# LF_SDD_AC_DC.net
KiCad netlist of a schematic drawn in Altium Designer
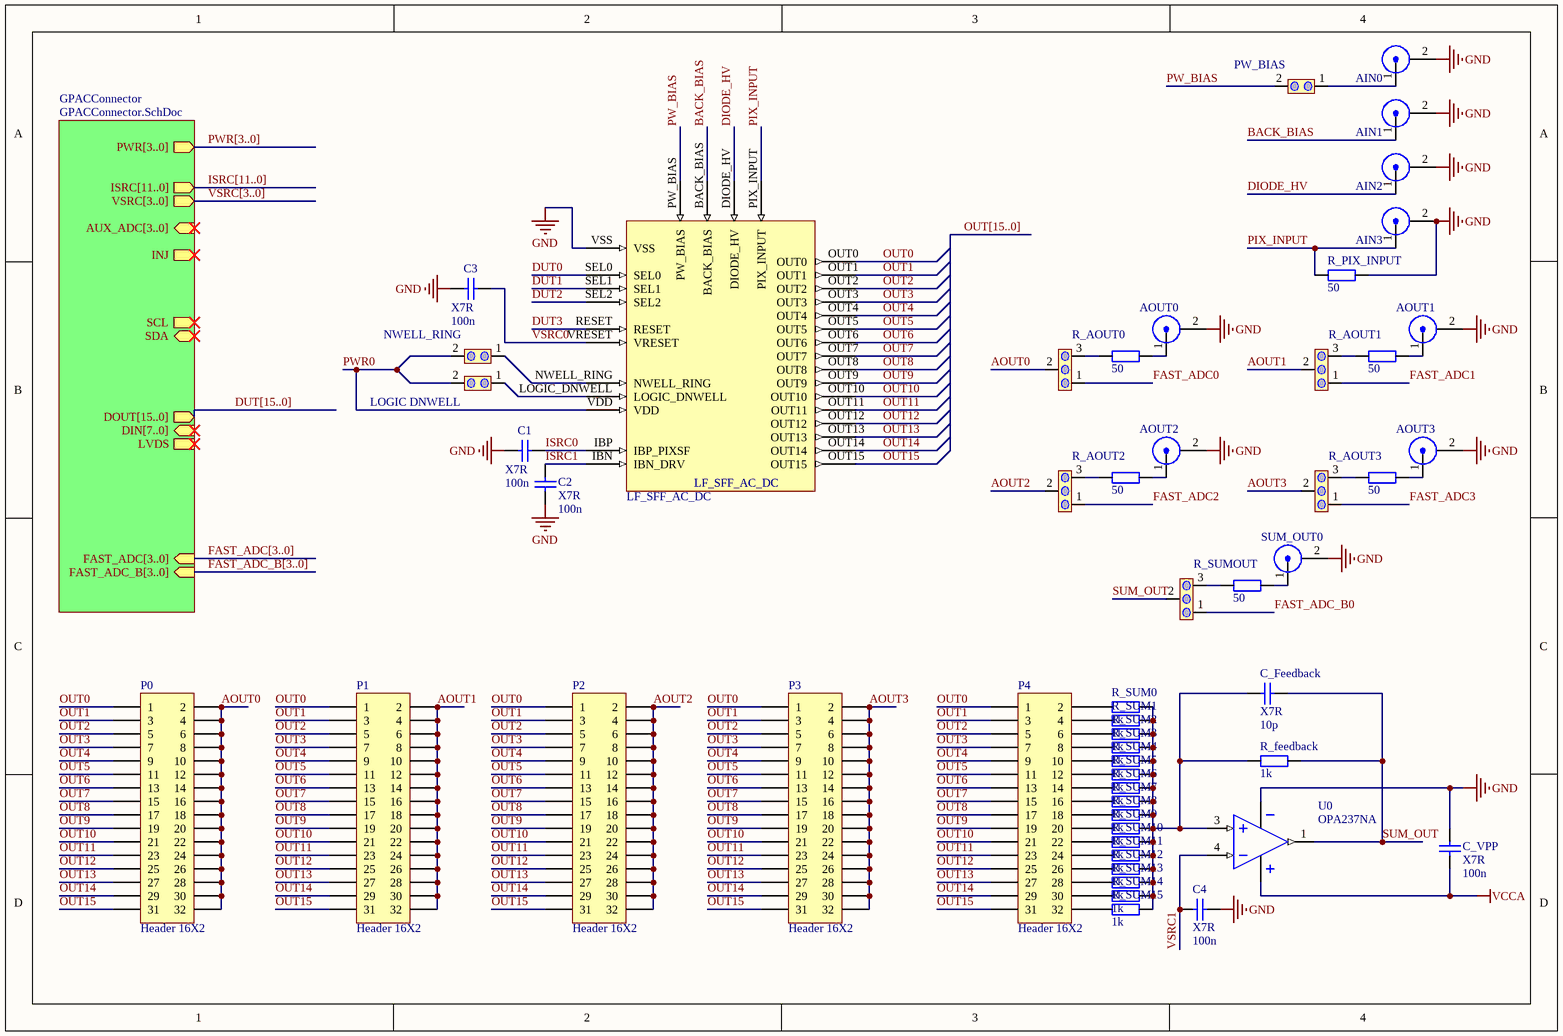
[diagram p0: LF_SDD_AC_DC.SchDoc]

(export (version "E")
  (design (tool "Eeschema 10.0.6"))
  (components
    (comp (ref "AIN0")
      (value "-")
      (footprint "LEMO horiz.")
      (description "LEMO/BNC Buchse, aufrecht od. gewinkelt")
      (fields (field (name "PUBLISHER") "Silab C.H."))
      (libsource (lib "Silab_Lib") (part "LEMO coax"))
    )
    (comp (ref "AIN1")
      (value "-")
      (footprint "LEMO horiz.")
      (description "LEMO/BNC Buchse, aufrecht od. gewinkelt")
      (fields (field (name "PUBLISHER") "Silab C.H."))
      (libsource (lib "Silab_Lib") (part "LEMO coax"))
    )
    (comp (ref "AIN2")
      (value "-")
      (footprint "LEMO horiz.")
      (description "LEMO/BNC Buchse, aufrecht od. gewinkelt")
      (fields (field (name "PUBLISHER") "Silab C.H."))
      (libsource (lib "Silab_Lib") (part "LEMO coax"))
    )
    (comp (ref "AIN3")
      (value "-")
      (footprint "LEMO horiz.")
      (description "LEMO/BNC Buchse, aufrecht od. gewinkelt")
      (fields (field (name "PUBLISHER") "Silab C.H."))
      (libsource (lib "Silab_Lib") (part "LEMO coax"))
    )
    (comp (ref "AOUT0")
      (value "-")
      (footprint "LEMO horiz.")
      (description "LEMO/BNC Buchse, aufrecht od. gewinkelt")
      (fields (field (name "PUBLISHER") "Silab C.H."))
      (libsource (lib "Silab_Lib") (part "LEMO coax"))
    )
    (comp (ref "AOUT1")
      (value "-")
      (footprint "LEMO horiz.")
      (description "LEMO/BNC Buchse, aufrecht od. gewinkelt")
      (fields (field (name "PUBLISHER") "Silab C.H."))
      (libsource (lib "Silab_Lib") (part "LEMO coax"))
    )
    (comp (ref "AOUT2")
      (value "-")
      (footprint "LEMO horiz.")
      (description "LEMO/BNC Buchse, aufrecht od. gewinkelt")
      (fields (field (name "PUBLISHER") "Silab C.H."))
      (libsource (lib "Silab_Lib") (part "LEMO coax"))
    )
    (comp (ref "AOUT3")
      (value "-")
      (footprint "LEMO horiz.")
      (description "LEMO/BNC Buchse, aufrecht od. gewinkelt")
      (fields (field (name "PUBLISHER") "Silab C.H."))
      (libsource (lib "Silab_Lib") (part "LEMO coax"))
    )
    (comp (ref "AOUT_SEL0")
      (value "-")
      (footprint "HDR 1x3")
      (description "Jumper, Solderbridge 1x3")
      (fields (field (name "PUBLISHER") "Silab C.H."))
      (libsource (lib "Silab_Lib") (part "JUMPER 1X3S"))
    )
    (comp (ref "AOUT_SEL1")
      (value "-")
      (footprint "HDR 1x3")
      (description "Jumper, Solderbridge 1x3")
      (fields (field (name "PUBLISHER") "Silab C.H."))
      (libsource (lib "Silab_Lib") (part "JUMPER 1X3S"))
    )
    (comp (ref "AOUT_SEL2")
      (value "-")
      (footprint "HDR 1x3")
      (description "Jumper, Solderbridge 1x3")
      (fields (field (name "PUBLISHER") "Silab C.H."))
      (libsource (lib "Silab_Lib") (part "JUMPER 1X3S"))
    )
    (comp (ref "AOUT_SEL3")
      (value "-")
      (footprint "HDR 1x3")
      (description "Jumper, Solderbridge 1x3")
      (fields (field (name "PUBLISHER") "Silab C.H."))
      (libsource (lib "Silab_Lib") (part "JUMPER 1X3S"))
    )
    (comp (ref "C1")
      (value "X7R")
      (footprint "C0603_imp_N")
      (description "Capacitor")
      (fields (field (name "ALTIUM_VALUE") "100n") (field (name "PUBLISHER") "Silab J.S."))
      (libsource (lib "Silab_Lib") (part "C"))
    )
    (comp (ref "C2")
      (value "X7R")
      (footprint "C0603_imp_N")
      (description "Capacitor")
      (fields (field (name "ALTIUM_VALUE") "100n") (field (name "PUBLISHER") "Silab J.S."))
      (libsource (lib "Silab_Lib") (part "C"))
    )
    (comp (ref "C3")
      (value "X7R")
      (footprint "C0603_imp_N")
      (description "Capacitor")
      (fields (field (name "ALTIUM_VALUE") "100n") (field (name "PUBLISHER") "Silab J.S."))
      (libsource (lib "Silab_Lib") (part "C"))
    )
    (comp (ref "C4")
      (value "X7R")
      (footprint "C0603_imp_N")
      (description "Capacitor")
      (fields (field (name "ALTIUM_VALUE") "100n") (field (name "PUBLISHER") "Silab J.S."))
      (libsource (lib "Silab_Lib") (part "C"))
    )
    (comp (ref "C_Feedback")
      (value "X7R")
      (footprint "C0603_imp_N")
      (description "Capacitor")
      (fields (field (name "ALTIUM_VALUE") "10p") (field (name "PUBLISHER") "Silab J.S."))
      (libsource (lib "Silab_Lib") (part "C"))
    )
    (comp (ref "C_VPP")
      (value "X7R")
      (footprint "C0603_imp_N")
      (description "Capacitor")
      (fields (field (name "ALTIUM_VALUE") "100n") (field (name "PUBLISHER") "Silab J.S."))
      (libsource (lib "Silab_Lib") (part "C"))
    )
    (comp (ref "LF_SFF_AC_DC")
      (value "LF_SFF_AC_DC")
      (footprint "LF_SFF_COMBI")
      (libsource (lib "LF_SFF_AC") (part "LF_SFF_AC"))
    )
    (comp (ref "LOGIC DNWELL")
      (value "-")
      (footprint "CON 1x2 std")
      (description "Jumper, Solderbridge 1x2")
      (fields (field (name "PUBLISHER") "Silab C.H."))
      (libsource (lib "Silab_Lib") (part "JUMPER 1X2S"))
    )
    (comp (ref "NWELL_RING")
      (value "-")
      (footprint "CON 1x2 std")
      (description "Jumper, Solderbridge 1x2")
      (fields (field (name "PUBLISHER") "Silab C.H."))
      (libsource (lib "Silab_Lib") (part "JUMPER 1X2S"))
    )
    (comp (ref "P0")
      (value "Header 16X2")
      (footprint "HDR2X16")
      (description "Header, 16-Pin, Dual row")
      (fields (field (name "PUBLISHER") "Altium Limited"))
      (libsource (lib "Miscellaneous Connectors") (part "Header 16X2"))
    )
    (comp (ref "P1")
      (value "Header 16X2")
      (footprint "HDR2X16")
      (description "Header, 16-Pin, Dual row")
      (fields (field (name "PUBLISHER") "Altium Limited"))
      (libsource (lib "Miscellaneous Connectors") (part "Header 16X2"))
    )
    (comp (ref "P2")
      (value "Header 16X2")
      (footprint "HDR2X16")
      (description "Header, 16-Pin, Dual row")
      (fields (field (name "PUBLISHER") "Altium Limited"))
      (libsource (lib "Miscellaneous Connectors") (part "Header 16X2"))
    )
    (comp (ref "P3")
      (value "Header 16X2")
      (footprint "HDR2X16")
      (description "Header, 16-Pin, Dual row")
      (fields (field (name "PUBLISHER") "Altium Limited"))
      (libsource (lib "Miscellaneous Connectors") (part "Header 16X2"))
    )
    (comp (ref "P4")
      (value "Header 16X2")
      (footprint "HDR2X16")
      (description "Header, 16-Pin, Dual row")
      (fields (field (name "PUBLISHER") "Altium Limited"))
      (libsource (lib "Miscellaneous Connectors") (part "Header 16X2"))
    )
    (comp (ref "PW_BIAS")
      (value "-")
      (footprint "CON 1x2 std")
      (description "Jumper, Solderbridge 1x2")
      (fields (field (name "PUBLISHER") "Silab C.H."))
      (libsource (lib "Silab_Lib") (part "JUMPER 1X2S"))
    )
    (comp (ref "R_AOUT0")
      (value "50")
      (footprint "R0603_imp_N")
      (description "SMD Chip Resistor")
      (fields (field (name "Comment") "R") (field (name "PUBLISHER") "Silab J.S."))
      (libsource (lib "Silab_Lib") (part "R"))
    )
    (comp (ref "R_AOUT1")
      (value "50")
      (footprint "R0603_imp_N")
      (description "SMD Chip Resistor")
      (fields (field (name "Comment") "R") (field (name "PUBLISHER") "Silab J.S."))
      (libsource (lib "Silab_Lib") (part "R"))
    )
    (comp (ref "R_AOUT2")
      (value "50")
      (footprint "R0603_imp_N")
      (description "SMD Chip Resistor")
      (fields (field (name "Comment") "R") (field (name "PUBLISHER") "Silab J.S."))
      (libsource (lib "Silab_Lib") (part "R"))
    )
    (comp (ref "R_AOUT3")
      (value "50")
      (footprint "R0603_imp_N")
      (description "SMD Chip Resistor")
      (fields (field (name "Comment") "R") (field (name "PUBLISHER") "Silab J.S."))
      (libsource (lib "Silab_Lib") (part "R"))
    )
    (comp (ref "R_feedback")
      (value "1k")
      (footprint "R0805_imp_M")
      (description "SMD Chip Resistor")
      (fields (field (name "Comment") "R") (field (name "PUBLISHER") "Silab J.S."))
      (libsource (lib "Silab_Lib") (part "R"))
    )
    (comp (ref "R_PIX_INPUT")
      (value "50")
      (footprint "R0603_imp_N")
      (description "SMD Chip Resistor")
      (fields (field (name "Comment") "R") (field (name "PUBLISHER") "Silab J.S."))
      (libsource (lib "Silab_Lib") (part "R"))
    )
    (comp (ref "R_SUM0")
      (value "1k")
      (footprint "R0805_imp_M")
      (description "SMD Chip Resistor")
      (fields (field (name "Comment") "R") (field (name "PUBLISHER") "Silab J.S."))
      (libsource (lib "Silab_Lib") (part "R"))
    )
    (comp (ref "R_SUM1")
      (value "1k")
      (footprint "R0805_imp_M")
      (description "SMD Chip Resistor")
      (fields (field (name "Comment") "R") (field (name "PUBLISHER") "Silab J.S."))
      (libsource (lib "Silab_Lib") (part "R"))
    )
    (comp (ref "R_SUM2")
      (value "1k")
      (footprint "R0805_imp_M")
      (description "SMD Chip Resistor")
      (fields (field (name "Comment") "R") (field (name "PUBLISHER") "Silab J.S."))
      (libsource (lib "Silab_Lib") (part "R"))
    )
    (comp (ref "R_SUM3")
      (value "1k")
      (footprint "R0805_imp_M")
      (description "SMD Chip Resistor")
      (fields (field (name "Comment") "R") (field (name "PUBLISHER") "Silab J.S."))
      (libsource (lib "Silab_Lib") (part "R"))
    )
    (comp (ref "R_SUM4")
      (value "1k")
      (footprint "R0805_imp_M")
      (description "SMD Chip Resistor")
      (fields (field (name "Comment") "R") (field (name "PUBLISHER") "Silab J.S."))
      (libsource (lib "Silab_Lib") (part "R"))
    )
    (comp (ref "R_SUM5")
      (value "1k")
      (footprint "R0805_imp_M")
      (description "SMD Chip Resistor")
      (fields (field (name "Comment") "R") (field (name "PUBLISHER") "Silab J.S."))
      (libsource (lib "Silab_Lib") (part "R"))
    )
    (comp (ref "R_SUM6")
      (value "1k")
      (footprint "R0805_imp_M")
      (description "SMD Chip Resistor")
      (fields (field (name "Comment") "R") (field (name "PUBLISHER") "Silab J.S."))
      (libsource (lib "Silab_Lib") (part "R"))
    )
    (comp (ref "R_SUM7")
      (value "1k")
      (footprint "R0805_imp_M")
      (description "SMD Chip Resistor")
      (fields (field (name "Comment") "R") (field (name "PUBLISHER") "Silab J.S."))
      (libsource (lib "Silab_Lib") (part "R"))
    )
    (comp (ref "R_SUM8")
      (value "1k")
      (footprint "R0805_imp_M")
      (description "SMD Chip Resistor")
      (fields (field (name "Comment") "R") (field (name "PUBLISHER") "Silab J.S."))
      (libsource (lib "Silab_Lib") (part "R"))
    )
    (comp (ref "R_SUM9")
      (value "1k")
      (footprint "R0805_imp_M")
      (description "SMD Chip Resistor")
      (fields (field (name "Comment") "R") (field (name "PUBLISHER") "Silab J.S."))
      (libsource (lib "Silab_Lib") (part "R"))
    )
    (comp (ref "R_SUM10")
      (value "1k")
      (footprint "R0805_imp_M")
      (description "SMD Chip Resistor")
      (fields (field (name "Comment") "R") (field (name "PUBLISHER") "Silab J.S."))
      (libsource (lib "Silab_Lib") (part "R"))
    )
    (comp (ref "R_SUM11")
      (value "1k")
      (footprint "R0805_imp_M")
      (description "SMD Chip Resistor")
      (fields (field (name "Comment") "R") (field (name "PUBLISHER") "Silab J.S."))
      (libsource (lib "Silab_Lib") (part "R"))
    )
    (comp (ref "R_SUM12")
      (value "1k")
      (footprint "R0805_imp_M")
      (description "SMD Chip Resistor")
      (fields (field (name "Comment") "R") (field (name "PUBLISHER") "Silab J.S."))
      (libsource (lib "Silab_Lib") (part "R"))
    )
    (comp (ref "R_SUM13")
      (value "1k")
      (footprint "R0805_imp_M")
      (description "SMD Chip Resistor")
      (fields (field (name "Comment") "R") (field (name "PUBLISHER") "Silab J.S."))
      (libsource (lib "Silab_Lib") (part "R"))
    )
    (comp (ref "R_SUM14")
      (value "1k")
      (footprint "R0805_imp_M")
      (description "SMD Chip Resistor")
      (fields (field (name "Comment") "R") (field (name "PUBLISHER") "Silab J.S."))
      (libsource (lib "Silab_Lib") (part "R"))
    )
    (comp (ref "R_SUM15")
      (value "1k")
      (footprint "R0805_imp_M")
      (description "SMD Chip Resistor")
      (fields (field (name "Comment") "R") (field (name "PUBLISHER") "Silab J.S."))
      (libsource (lib "Silab_Lib") (part "R"))
    )
    (comp (ref "R_SUMOUT")
      (value "50")
      (footprint "R0603_imp_N")
      (description "SMD Chip Resistor")
      (fields (field (name "Comment") "R") (field (name "PUBLISHER") "Silab J.S."))
      (libsource (lib "Silab_Lib") (part "R"))
    )
    (comp (ref "SUM_OUT0")
      (value "-")
      (footprint "LEMO horiz.")
      (description "LEMO/BNC Buchse, aufrecht od. gewinkelt")
      (fields (field (name "PUBLISHER") "Silab C.H."))
      (libsource (lib "Silab_Lib") (part "LEMO coax"))
    )
    (comp (ref "SUM_SELECT")
      (value "-")
      (footprint "HDR 1x3")
      (description "Jumper, Solderbridge 1x3")
      (fields (field (name "PUBLISHER") "Silab C.H."))
      (libsource (lib "Silab_Lib") (part "JUMPER 1X3S"))
    )
    (comp (ref "U0")
      (value "OPA237")
      (footprint "SOT23-5")
      (description "OpAmp (TI), single supply up to +36V;")
      (fields (field (name "TYPE_1") "OPA237NA") (field (name "PUBLISHER") "Silab J.S."))
      (libsource (lib "Silab_Lib") (part "OPA237"))
    )
  )
  (nets
    (net (code "31") (name "/AOUT0") (class "Default")
      (node (ref "AOUT_SEL0") (pin "2") (pinfunction "2_2") (pintype "passive"))
      (node (ref "P0") (pin "10") (pinfunction "10_10") (pintype "passive"))
      (node (ref "P0") (pin "12") (pinfunction "12_12") (pintype "passive"))
      (node (ref "P0") (pin "14") (pinfunction "14_14") (pintype "passive"))
      (node (ref "P0") (pin "16") (pinfunction "16_16") (pintype "passive"))
      (node (ref "P0") (pin "18") (pinfunction "18_18") (pintype "passive"))
      (node (ref "P0") (pin "2") (pinfunction "2_2") (pintype "passive"))
      (node (ref "P0") (pin "20") (pinfunction "20_20") (pintype "passive"))
      (node (ref "P0") (pin "22") (pinfunction "22_22") (pintype "passive"))
      (node (ref "P0") (pin "24") (pinfunction "24_24") (pintype "passive"))
      (node (ref "P0") (pin "26") (pinfunction "26_26") (pintype "passive"))
      (node (ref "P0") (pin "28") (pinfunction "28_28") (pintype "passive"))
      (node (ref "P0") (pin "30") (pinfunction "30_30") (pintype "passive"))
      (node (ref "P0") (pin "32") (pinfunction "32_32") (pintype "passive"))
      (node (ref "P0") (pin "4") (pinfunction "4_4") (pintype "passive"))
      (node (ref "P0") (pin "6") (pinfunction "6_6") (pintype "passive"))
      (node (ref "P0") (pin "8") (pinfunction "8_8") (pintype "passive"))
    )
    (net (code "32") (name "/AOUT1") (class "Default")
      (node (ref "AOUT_SEL1") (pin "2") (pinfunction "2_2") (pintype "passive"))
      (node (ref "P1") (pin "10") (pinfunction "10_10") (pintype "passive"))
      (node (ref "P1") (pin "12") (pinfunction "12_12") (pintype "passive"))
      (node (ref "P1") (pin "14") (pinfunction "14_14") (pintype "passive"))
      (node (ref "P1") (pin "16") (pinfunction "16_16") (pintype "passive"))
      (node (ref "P1") (pin "18") (pinfunction "18_18") (pintype "passive"))
      (node (ref "P1") (pin "2") (pinfunction "2_2") (pintype "passive"))
      (node (ref "P1") (pin "20") (pinfunction "20_20") (pintype "passive"))
      (node (ref "P1") (pin "22") (pinfunction "22_22") (pintype "passive"))
      (node (ref "P1") (pin "24") (pinfunction "24_24") (pintype "passive"))
      (node (ref "P1") (pin "26") (pinfunction "26_26") (pintype "passive"))
      (node (ref "P1") (pin "28") (pinfunction "28_28") (pintype "passive"))
      (node (ref "P1") (pin "30") (pinfunction "30_30") (pintype "passive"))
      (node (ref "P1") (pin "32") (pinfunction "32_32") (pintype "passive"))
      (node (ref "P1") (pin "4") (pinfunction "4_4") (pintype "passive"))
      (node (ref "P1") (pin "6") (pinfunction "6_6") (pintype "passive"))
      (node (ref "P1") (pin "8") (pinfunction "8_8") (pintype "passive"))
    )
    (net (code "33") (name "/AOUT2") (class "Default")
      (node (ref "AOUT_SEL2") (pin "2") (pinfunction "2_2") (pintype "passive"))
      (node (ref "P2") (pin "10") (pinfunction "10_10") (pintype "passive"))
      (node (ref "P2") (pin "12") (pinfunction "12_12") (pintype "passive"))
      (node (ref "P2") (pin "14") (pinfunction "14_14") (pintype "passive"))
      (node (ref "P2") (pin "16") (pinfunction "16_16") (pintype "passive"))
      (node (ref "P2") (pin "18") (pinfunction "18_18") (pintype "passive"))
      (node (ref "P2") (pin "2") (pinfunction "2_2") (pintype "passive"))
      (node (ref "P2") (pin "20") (pinfunction "20_20") (pintype "passive"))
      (node (ref "P2") (pin "22") (pinfunction "22_22") (pintype "passive"))
      (node (ref "P2") (pin "24") (pinfunction "24_24") (pintype "passive"))
      (node (ref "P2") (pin "26") (pinfunction "26_26") (pintype "passive"))
      (node (ref "P2") (pin "28") (pinfunction "28_28") (pintype "passive"))
      (node (ref "P2") (pin "30") (pinfunction "30_30") (pintype "passive"))
      (node (ref "P2") (pin "32") (pinfunction "32_32") (pintype "passive"))
      (node (ref "P2") (pin "4") (pinfunction "4_4") (pintype "passive"))
      (node (ref "P2") (pin "6") (pinfunction "6_6") (pintype "passive"))
      (node (ref "P2") (pin "8") (pinfunction "8_8") (pintype "passive"))
    )
    (net (code "34") (name "/AOUT3") (class "Default")
      (node (ref "AOUT_SEL3") (pin "2") (pinfunction "2_2") (pintype "passive"))
      (node (ref "P3") (pin "10") (pinfunction "10_10") (pintype "passive"))
      (node (ref "P3") (pin "12") (pinfunction "12_12") (pintype "passive"))
      (node (ref "P3") (pin "14") (pinfunction "14_14") (pintype "passive"))
      (node (ref "P3") (pin "16") (pinfunction "16_16") (pintype "passive"))
      (node (ref "P3") (pin "18") (pinfunction "18_18") (pintype "passive"))
      (node (ref "P3") (pin "2") (pinfunction "2_2") (pintype "passive"))
      (node (ref "P3") (pin "20") (pinfunction "20_20") (pintype "passive"))
      (node (ref "P3") (pin "22") (pinfunction "22_22") (pintype "passive"))
      (node (ref "P3") (pin "24") (pinfunction "24_24") (pintype "passive"))
      (node (ref "P3") (pin "26") (pinfunction "26_26") (pintype "passive"))
      (node (ref "P3") (pin "28") (pinfunction "28_28") (pintype "passive"))
      (node (ref "P3") (pin "30") (pinfunction "30_30") (pintype "passive"))
      (node (ref "P3") (pin "32") (pinfunction "32_32") (pintype "passive"))
      (node (ref "P3") (pin "4") (pinfunction "4_4") (pintype "passive"))
      (node (ref "P3") (pin "6") (pinfunction "6_6") (pintype "passive"))
      (node (ref "P3") (pin "8") (pinfunction "8_8") (pintype "passive"))
    )
    (net (code "36") (name "/BACK_BIAS") (class "Default")
      (node (ref "AIN1") (pin "1") (pinfunction "1_1") (pintype "passive"))
      (node (ref "LF_SFF_AC_DC") (pin "BACK_BIAS") (pinfunction "BACK_BIAS_BACK_BIAS") (pintype "input"))
    )
    (net (code "38") (name "/DIODE_HV") (class "Default")
      (node (ref "AIN2") (pin "1") (pinfunction "1_1") (pintype "passive"))
      (node (ref "LF_SFF_AC_DC") (pin "DIODE_HV") (pinfunction "DIODE_HV_DIODE_HV") (pintype "input"))
    )
    (net (code "39") (name "/DUT0") (class "Default")
      (node (ref "LF_SFF_AC_DC") (pin "SEL0") (pinfunction "SEL0_SEL0") (pintype "input"))
    )
    (net (code "40") (name "/DUT1") (class "Default")
      (node (ref "LF_SFF_AC_DC") (pin "SEL1") (pinfunction "SEL1_SEL1") (pintype "input"))
    )
    (net (code "41") (name "/DUT2") (class "Default")
      (node (ref "LF_SFF_AC_DC") (pin "SEL2") (pinfunction "SEL2_SEL2") (pintype "input"))
    )
    (net (code "42") (name "/DUT3") (class "Default")
      (node (ref "LF_SFF_AC_DC") (pin "RESET") (pinfunction "RESET_RESET") (pintype "input"))
    )
    (net (code "44") (name "/FAST_ADC0") (class "Default")
      (node (ref "AOUT_SEL0") (pin "1") (pinfunction "1_1") (pintype "passive"))
    )
    (net (code "45") (name "/FAST_ADC1") (class "Default")
      (node (ref "AOUT_SEL1") (pin "1") (pinfunction "1_1") (pintype "passive"))
    )
    (net (code "46") (name "/FAST_ADC2") (class "Default")
      (node (ref "AOUT_SEL2") (pin "1") (pinfunction "1_1") (pintype "passive"))
    )
    (net (code "47") (name "/FAST_ADC3") (class "Default")
      (node (ref "AOUT_SEL3") (pin "1") (pinfunction "1_1") (pintype "passive"))
    )
    (net (code "49") (name "/FAST_ADC_B0") (class "Default")
      (node (ref "SUM_SELECT") (pin "1") (pinfunction "1_1") (pintype "passive"))
    )
    (net (code "52") (name "/ISRC0") (class "Default")
      (node (ref "C1") (pin "1") (pinfunction "1_1") (pintype "passive"))
      (node (ref "LF_SFF_AC_DC") (pin "IBP") (pinfunction "IBP_PIXSF_IBP") (pintype "input"))
    )
    (net (code "53") (name "/ISRC1") (class "Default")
      (node (ref "C2") (pin "1") (pinfunction "1_1") (pintype "passive"))
      (node (ref "LF_SFF_AC_DC") (pin "IBN") (pinfunction "IBN_DRV_IBN") (pintype "input"))
    )
    (net (code "56") (name "/OUT0") (class "Default")
      (node (ref "LF_SFF_AC_DC") (pin "OUT0") (pinfunction "OUT0_OUT0") (pintype "output"))
      (node (ref "P0") (pin "1") (pinfunction "1_1") (pintype "passive"))
      (node (ref "P1") (pin "1") (pinfunction "1_1") (pintype "passive"))
      (node (ref "P2") (pin "1") (pinfunction "1_1") (pintype "passive"))
      (node (ref "P3") (pin "1") (pinfunction "1_1") (pintype "passive"))
      (node (ref "P4") (pin "1") (pinfunction "1_1") (pintype "passive"))
    )
    (net (code "57") (name "/OUT1") (class "Default")
      (node (ref "LF_SFF_AC_DC") (pin "OUT1") (pinfunction "OUT1_OUT1") (pintype "output"))
      (node (ref "P0") (pin "3") (pinfunction "3_3") (pintype "passive"))
      (node (ref "P1") (pin "3") (pinfunction "3_3") (pintype "passive"))
      (node (ref "P2") (pin "3") (pinfunction "3_3") (pintype "passive"))
      (node (ref "P3") (pin "3") (pinfunction "3_3") (pintype "passive"))
      (node (ref "P4") (pin "3") (pinfunction "3_3") (pintype "passive"))
    )
    (net (code "58") (name "/OUT2") (class "Default")
      (node (ref "LF_SFF_AC_DC") (pin "OUT2") (pinfunction "OUT2_OUT2") (pintype "output"))
      (node (ref "P0") (pin "5") (pinfunction "5_5") (pintype "passive"))
      (node (ref "P1") (pin "5") (pinfunction "5_5") (pintype "passive"))
      (node (ref "P2") (pin "5") (pinfunction "5_5") (pintype "passive"))
      (node (ref "P3") (pin "5") (pinfunction "5_5") (pintype "passive"))
      (node (ref "P4") (pin "5") (pinfunction "5_5") (pintype "passive"))
    )
    (net (code "59") (name "/OUT3") (class "Default")
      (node (ref "LF_SFF_AC_DC") (pin "OUT3") (pinfunction "OUT3_OUT3") (pintype "output"))
      (node (ref "P0") (pin "7") (pinfunction "7_7") (pintype "passive"))
      (node (ref "P1") (pin "7") (pinfunction "7_7") (pintype "passive"))
      (node (ref "P2") (pin "7") (pinfunction "7_7") (pintype "passive"))
      (node (ref "P3") (pin "7") (pinfunction "7_7") (pintype "passive"))
      (node (ref "P4") (pin "7") (pinfunction "7_7") (pintype "passive"))
    )
    (net (code "60") (name "/OUT4") (class "Default")
      (node (ref "LF_SFF_AC_DC") (pin "OUT4") (pinfunction "OUT4_OUT4") (pintype "output"))
      (node (ref "P0") (pin "9") (pinfunction "9_9") (pintype "passive"))
      (node (ref "P1") (pin "9") (pinfunction "9_9") (pintype "passive"))
      (node (ref "P2") (pin "9") (pinfunction "9_9") (pintype "passive"))
      (node (ref "P3") (pin "9") (pinfunction "9_9") (pintype "passive"))
      (node (ref "P4") (pin "9") (pinfunction "9_9") (pintype "passive"))
    )
    (net (code "61") (name "/OUT5") (class "Default")
      (node (ref "LF_SFF_AC_DC") (pin "OUT5") (pinfunction "OUT5_OUT5") (pintype "output"))
      (node (ref "P0") (pin "11") (pinfunction "11_11") (pintype "passive"))
      (node (ref "P1") (pin "11") (pinfunction "11_11") (pintype "passive"))
      (node (ref "P2") (pin "11") (pinfunction "11_11") (pintype "passive"))
      (node (ref "P3") (pin "11") (pinfunction "11_11") (pintype "passive"))
      (node (ref "P4") (pin "11") (pinfunction "11_11") (pintype "passive"))
    )
    (net (code "62") (name "/OUT6") (class "Default")
      (node (ref "LF_SFF_AC_DC") (pin "OUT6") (pinfunction "OUT6_OUT6") (pintype "output"))
      (node (ref "P0") (pin "13") (pinfunction "13_13") (pintype "passive"))
      (node (ref "P1") (pin "13") (pinfunction "13_13") (pintype "passive"))
      (node (ref "P2") (pin "13") (pinfunction "13_13") (pintype "passive"))
      (node (ref "P3") (pin "13") (pinfunction "13_13") (pintype "passive"))
      (node (ref "P4") (pin "13") (pinfunction "13_13") (pintype "passive"))
    )
    (net (code "63") (name "/OUT7") (class "Default")
      (node (ref "LF_SFF_AC_DC") (pin "OUT7") (pinfunction "OUT7_OUT7") (pintype "output"))
      (node (ref "P0") (pin "15") (pinfunction "15_15") (pintype "passive"))
      (node (ref "P1") (pin "15") (pinfunction "15_15") (pintype "passive"))
      (node (ref "P2") (pin "15") (pinfunction "15_15") (pintype "passive"))
      (node (ref "P3") (pin "15") (pinfunction "15_15") (pintype "passive"))
      (node (ref "P4") (pin "15") (pinfunction "15_15") (pintype "passive"))
    )
    (net (code "64") (name "/OUT8") (class "Default")
      (node (ref "LF_SFF_AC_DC") (pin "OUT8") (pinfunction "OUT8_OUT8") (pintype "output"))
      (node (ref "P0") (pin "17") (pinfunction "17_17") (pintype "passive"))
      (node (ref "P1") (pin "17") (pinfunction "17_17") (pintype "passive"))
      (node (ref "P2") (pin "17") (pinfunction "17_17") (pintype "passive"))
      (node (ref "P3") (pin "17") (pinfunction "17_17") (pintype "passive"))
      (node (ref "P4") (pin "17") (pinfunction "17_17") (pintype "passive"))
    )
    (net (code "65") (name "/OUT9") (class "Default")
      (node (ref "LF_SFF_AC_DC") (pin "OUT9") (pinfunction "OUT9_OUT9") (pintype "output"))
      (node (ref "P0") (pin "19") (pinfunction "19_19") (pintype "passive"))
      (node (ref "P1") (pin "19") (pinfunction "19_19") (pintype "passive"))
      (node (ref "P2") (pin "19") (pinfunction "19_19") (pintype "passive"))
      (node (ref "P3") (pin "19") (pinfunction "19_19") (pintype "passive"))
      (node (ref "P4") (pin "19") (pinfunction "19_19") (pintype "passive"))
    )
    (net (code "66") (name "/OUT10") (class "Default")
      (node (ref "LF_SFF_AC_DC") (pin "OUT10") (pinfunction "OUT10_OUT10") (pintype "output"))
      (node (ref "P0") (pin "21") (pinfunction "21_21") (pintype "passive"))
      (node (ref "P1") (pin "21") (pinfunction "21_21") (pintype "passive"))
      (node (ref "P2") (pin "21") (pinfunction "21_21") (pintype "passive"))
      (node (ref "P3") (pin "21") (pinfunction "21_21") (pintype "passive"))
      (node (ref "P4") (pin "21") (pinfunction "21_21") (pintype "passive"))
    )
    (net (code "67") (name "/OUT11") (class "Default")
      (node (ref "LF_SFF_AC_DC") (pin "OUT11") (pinfunction "OUT11_OUT11") (pintype "output"))
      (node (ref "P0") (pin "23") (pinfunction "23_23") (pintype "passive"))
      (node (ref "P1") (pin "23") (pinfunction "23_23") (pintype "passive"))
      (node (ref "P2") (pin "23") (pinfunction "23_23") (pintype "passive"))
      (node (ref "P3") (pin "23") (pinfunction "23_23") (pintype "passive"))
      (node (ref "P4") (pin "23") (pinfunction "23_23") (pintype "passive"))
    )
    (net (code "68") (name "/OUT12") (class "Default")
      (node (ref "LF_SFF_AC_DC") (pin "OUT12") (pinfunction "OUT12_OUT12") (pintype "output"))
      (node (ref "P0") (pin "25") (pinfunction "25_25") (pintype "passive"))
      (node (ref "P1") (pin "25") (pinfunction "25_25") (pintype "passive"))
      (node (ref "P2") (pin "25") (pinfunction "25_25") (pintype "passive"))
      (node (ref "P3") (pin "25") (pinfunction "25_25") (pintype "passive"))
      (node (ref "P4") (pin "25") (pinfunction "25_25") (pintype "passive"))
    )
    (net (code "69") (name "/OUT13") (class "Default")
      (node (ref "LF_SFF_AC_DC") (pin "OUT13") (pinfunction "OUT13_OUT13") (pintype "output"))
      (node (ref "P0") (pin "27") (pinfunction "27_27") (pintype "passive"))
      (node (ref "P1") (pin "27") (pinfunction "27_27") (pintype "passive"))
      (node (ref "P2") (pin "27") (pinfunction "27_27") (pintype "passive"))
      (node (ref "P3") (pin "27") (pinfunction "27_27") (pintype "passive"))
      (node (ref "P4") (pin "27") (pinfunction "27_27") (pintype "passive"))
    )
    (net (code "70") (name "/OUT14") (class "Default")
      (node (ref "LF_SFF_AC_DC") (pin "OUT14") (pinfunction "OUT14_OUT14") (pintype "output"))
      (node (ref "P0") (pin "29") (pinfunction "29_29") (pintype "passive"))
      (node (ref "P1") (pin "29") (pinfunction "29_29") (pintype "passive"))
      (node (ref "P2") (pin "29") (pinfunction "29_29") (pintype "passive"))
      (node (ref "P3") (pin "29") (pinfunction "29_29") (pintype "passive"))
      (node (ref "P4") (pin "29") (pinfunction "29_29") (pintype "passive"))
    )
    (net (code "71") (name "/OUT15") (class "Default")
      (node (ref "LF_SFF_AC_DC") (pin "OUT15") (pinfunction "OUT15_OUT15") (pintype "output"))
      (node (ref "P0") (pin "31") (pinfunction "31_31") (pintype "passive"))
      (node (ref "P1") (pin "31") (pinfunction "31_31") (pintype "passive"))
      (node (ref "P2") (pin "31") (pinfunction "31_31") (pintype "passive"))
      (node (ref "P3") (pin "31") (pinfunction "31_31") (pintype "passive"))
      (node (ref "P4") (pin "31") (pinfunction "31_31") (pintype "passive"))
    )
    (net (code "73") (name "/PIX_INPUT") (class "Default")
      (node (ref "AIN3") (pin "1") (pinfunction "1_1") (pintype "passive"))
      (node (ref "LF_SFF_AC_DC") (pin "PIX_INPUT") (pinfunction "PIX_INPUT_PIX_INPUT") (pintype "input"))
      (node (ref "R_PIX_INPUT") (pin "1") (pinfunction "1_1") (pintype "passive"))
    )
    (net (code "74") (name "/PWR0") (class "Default")
      (node (ref "LF_SFF_AC_DC") (pin "VDD") (pinfunction "VDD_VDD") (pintype "input"))
      (node (ref "LOGIC DNWELL") (pin "2") (pinfunction "2_2") (pintype "passive"))
      (node (ref "NWELL_RING") (pin "2") (pinfunction "2_2") (pintype "passive"))
    )
    (net (code "76") (name "/PW_BIAS") (class "Default")
      (node (ref "LF_SFF_AC_DC") (pin "PW_BIAS") (pinfunction "PW_BIAS_PW_BIAS") (pintype "input"))
      (node (ref "PW_BIAS") (pin "2") (pinfunction "2_2") (pintype "passive"))
    )
    (net (code "79") (name "/SUM_OUT") (class "Default")
      (node (ref "C_Feedback") (pin "2") (pinfunction "2_2") (pintype "passive"))
      (node (ref "R_feedback") (pin "2") (pinfunction "2_2") (pintype "passive"))
      (node (ref "SUM_SELECT") (pin "2") (pinfunction "2_2") (pintype "passive"))
      (node (ref "U0") (pin "1") (pinfunction "OUT_1") (pintype "output"))
    )
    (net (code "80") (name "/VSRC0") (class "Default")
      (node (ref "C3") (pin "1") (pinfunction "1_1") (pintype "passive"))
      (node (ref "LF_SFF_AC_DC") (pin "VRESET") (pinfunction "VRESET_VRESET") (pintype "input"))
    )
    (net (code "81") (name "/VSRC1") (class "Default")
      (node (ref "C4") (pin "1") (pinfunction "1_1") (pintype "passive"))
      (node (ref "U0") (pin "4") (pinfunction "IN-_4") (pintype "input"))
    )
    (net (code "83") (name "GND") (class "Default")
      (node (ref "AIN0") (pin "2") (pinfunction "2_2") (pintype "passive"))
      (node (ref "AIN1") (pin "2") (pinfunction "2_2") (pintype "passive"))
      (node (ref "AIN2") (pin "2") (pinfunction "2_2") (pintype "passive"))
      (node (ref "AIN3") (pin "2") (pinfunction "2_2") (pintype "passive"))
      (node (ref "AOUT0") (pin "2") (pinfunction "2_2") (pintype "passive"))
      (node (ref "AOUT1") (pin "2") (pinfunction "2_2") (pintype "passive"))
      (node (ref "AOUT2") (pin "2") (pinfunction "2_2") (pintype "passive"))
      (node (ref "AOUT3") (pin "2") (pinfunction "2_2") (pintype "passive"))
      (node (ref "C1") (pin "2") (pinfunction "2_2") (pintype "passive"))
      (node (ref "C2") (pin "2") (pinfunction "2_2") (pintype "passive"))
      (node (ref "C3") (pin "2") (pinfunction "2_2") (pintype "passive"))
      (node (ref "C4") (pin "2") (pinfunction "2_2") (pintype "passive"))
      (node (ref "C_VPP") (pin "1") (pinfunction "1_1") (pintype "passive"))
      (node (ref "LF_SFF_AC_DC") (pin "VSS") (pinfunction "VSS_VSS") (pintype "input"))
      (node (ref "R_PIX_INPUT") (pin "2") (pinfunction "2_2") (pintype "passive"))
      (node (ref "SUM_OUT0") (pin "2") (pinfunction "2_2") (pintype "passive"))
      (node (ref "U0") (pin "2") (pinfunction "V-_2") (pintype "power_in"))
    )
    (net (code "84") (name "Net-(AIN0-Pad1)") (class "Default")
      (node (ref "AIN0") (pin "1") (pinfunction "1_1") (pintype "passive"))
      (node (ref "PW_BIAS") (pin "1") (pinfunction "1_1") (pintype "passive"))
    )
    (net (code "85") (name "Net-(AOUT0-Pad1)") (class "Default")
      (node (ref "AOUT0") (pin "1") (pinfunction "1_1") (pintype "passive"))
      (node (ref "R_AOUT0") (pin "1") (pinfunction "1_1") (pintype "passive"))
    )
    (net (code "86") (name "Net-(AOUT1-Pad1)") (class "Default")
      (node (ref "AOUT1") (pin "1") (pinfunction "1_1") (pintype "passive"))
      (node (ref "R_AOUT1") (pin "1") (pinfunction "1_1") (pintype "passive"))
    )
    (net (code "87") (name "Net-(AOUT2-Pad1)") (class "Default")
      (node (ref "AOUT2") (pin "1") (pinfunction "1_1") (pintype "passive"))
      (node (ref "R_AOUT2") (pin "1") (pinfunction "1_1") (pintype "passive"))
    )
    (net (code "88") (name "Net-(AOUT3-Pad1)") (class "Default")
      (node (ref "AOUT3") (pin "1") (pinfunction "1_1") (pintype "passive"))
      (node (ref "R_AOUT3") (pin "1") (pinfunction "1_1") (pintype "passive"))
    )
    (net (code "89") (name "Net-(AOUT_SEL0-Pad3)") (class "Default")
      (node (ref "AOUT_SEL0") (pin "3") (pinfunction "3_3") (pintype "passive"))
      (node (ref "R_AOUT0") (pin "2") (pinfunction "2_2") (pintype "passive"))
    )
    (net (code "90") (name "Net-(AOUT_SEL1-Pad3)") (class "Default")
      (node (ref "AOUT_SEL1") (pin "3") (pinfunction "3_3") (pintype "passive"))
      (node (ref "R_AOUT1") (pin "2") (pinfunction "2_2") (pintype "passive"))
    )
    (net (code "91") (name "Net-(AOUT_SEL2-Pad3)") (class "Default")
      (node (ref "AOUT_SEL2") (pin "3") (pinfunction "3_3") (pintype "passive"))
      (node (ref "R_AOUT2") (pin "2") (pinfunction "2_2") (pintype "passive"))
    )
    (net (code "92") (name "Net-(AOUT_SEL3-Pad3)") (class "Default")
      (node (ref "AOUT_SEL3") (pin "3") (pinfunction "3_3") (pintype "passive"))
      (node (ref "R_AOUT3") (pin "2") (pinfunction "2_2") (pintype "passive"))
    )
    (net (code "93") (name "Net-(LF_SFF_AC_DC-PadLOGIC_DNWELL)") (class "Default")
      (node (ref "LF_SFF_AC_DC") (pin "LOGIC_DNWELL") (pinfunction "LOGIC_DNWELL_LOGIC_DNWELL") (pintype "input"))
      (node (ref "LOGIC DNWELL") (pin "1") (pinfunction "1_1") (pintype "passive"))
    )
    (net (code "94") (name "Net-(LF_SFF_AC_DC-PadNWELL_RING)") (class "Default")
      (node (ref "LF_SFF_AC_DC") (pin "NWELL_RING") (pinfunction "NWELL_RING_NWELL_RING") (pintype "input"))
      (node (ref "NWELL_RING") (pin "1") (pinfunction "1_1") (pintype "passive"))
    )
    (net (code "95") (name "Net-(P4-Pad2)") (class "Default")
      (node (ref "P4") (pin "2") (pinfunction "2_2") (pintype "passive"))
      (node (ref "R_SUM0") (pin "1") (pinfunction "1_1") (pintype "passive"))
    )
    (net (code "96") (name "Net-(P4-Pad4)") (class "Default")
      (node (ref "P4") (pin "4") (pinfunction "4_4") (pintype "passive"))
      (node (ref "R_SUM1") (pin "1") (pinfunction "1_1") (pintype "passive"))
    )
    (net (code "97") (name "Net-(P4-Pad6)") (class "Default")
      (node (ref "P4") (pin "6") (pinfunction "6_6") (pintype "passive"))
      (node (ref "R_SUM2") (pin "1") (pinfunction "1_1") (pintype "passive"))
    )
    (net (code "98") (name "Net-(P4-Pad8)") (class "Default")
      (node (ref "P4") (pin "8") (pinfunction "8_8") (pintype "passive"))
      (node (ref "R_SUM3") (pin "1") (pinfunction "1_1") (pintype "passive"))
    )
    (net (code "99") (name "Net-(P4-Pad10)") (class "Default")
      (node (ref "P4") (pin "10") (pinfunction "10_10") (pintype "passive"))
      (node (ref "R_SUM4") (pin "1") (pinfunction "1_1") (pintype "passive"))
    )
    (net (code "100") (name "Net-(P4-Pad12)") (class "Default")
      (node (ref "P4") (pin "12") (pinfunction "12_12") (pintype "passive"))
      (node (ref "R_SUM5") (pin "1") (pinfunction "1_1") (pintype "passive"))
    )
    (net (code "101") (name "Net-(P4-Pad14)") (class "Default")
      (node (ref "P4") (pin "14") (pinfunction "14_14") (pintype "passive"))
      (node (ref "R_SUM6") (pin "1") (pinfunction "1_1") (pintype "passive"))
    )
    (net (code "102") (name "Net-(P4-Pad16)") (class "Default")
      (node (ref "P4") (pin "16") (pinfunction "16_16") (pintype "passive"))
      (node (ref "R_SUM7") (pin "1") (pinfunction "1_1") (pintype "passive"))
    )
    (net (code "103") (name "Net-(P4-Pad18)") (class "Default")
      (node (ref "P4") (pin "18") (pinfunction "18_18") (pintype "passive"))
      (node (ref "R_SUM8") (pin "1") (pinfunction "1_1") (pintype "passive"))
    )
    (net (code "104") (name "Net-(P4-Pad20)") (class "Default")
      (node (ref "P4") (pin "20") (pinfunction "20_20") (pintype "passive"))
      (node (ref "R_SUM9") (pin "1") (pinfunction "1_1") (pintype "passive"))
    )
    (net (code "105") (name "Net-(P4-Pad22)") (class "Default")
      (node (ref "P4") (pin "22") (pinfunction "22_22") (pintype "passive"))
      (node (ref "R_SUM10") (pin "1") (pinfunction "1_1") (pintype "passive"))
    )
    (net (code "106") (name "Net-(P4-Pad24)") (class "Default")
      (node (ref "P4") (pin "24") (pinfunction "24_24") (pintype "passive"))
      (node (ref "R_SUM11") (pin "1") (pinfunction "1_1") (pintype "passive"))
    )
    (net (code "107") (name "Net-(P4-Pad26)") (class "Default")
      (node (ref "P4") (pin "26") (pinfunction "26_26") (pintype "passive"))
      (node (ref "R_SUM12") (pin "1") (pinfunction "1_1") (pintype "passive"))
    )
    (net (code "108") (name "Net-(P4-Pad28)") (class "Default")
      (node (ref "P4") (pin "28") (pinfunction "28_28") (pintype "passive"))
      (node (ref "R_SUM13") (pin "1") (pinfunction "1_1") (pintype "passive"))
    )
    (net (code "109") (name "Net-(P4-Pad30)") (class "Default")
      (node (ref "P4") (pin "30") (pinfunction "30_30") (pintype "passive"))
      (node (ref "R_SUM14") (pin "1") (pinfunction "1_1") (pintype "passive"))
    )
    (net (code "110") (name "Net-(P4-Pad32)") (class "Default")
      (node (ref "P4") (pin "32") (pinfunction "32_32") (pintype "passive"))
      (node (ref "R_SUM15") (pin "1") (pinfunction "1_1") (pintype "passive"))
    )
    (net (code "111") (name "Net-(R_SUMOUT-Pad1)") (class "Default")
      (node (ref "R_SUMOUT") (pin "1") (pinfunction "1_1") (pintype "passive"))
      (node (ref "SUM_OUT0") (pin "1") (pinfunction "1_1") (pintype "passive"))
    )
    (net (code "112") (name "Net-(R_SUMOUT-Pad2)") (class "Default")
      (node (ref "R_SUMOUT") (pin "2") (pinfunction "2_2") (pintype "passive"))
      (node (ref "SUM_SELECT") (pin "3") (pinfunction "3_3") (pintype "passive"))
    )
    (net (code "113") (name "Net-(U0-IN+)") (class "Default")
      (node (ref "C_Feedback") (pin "1") (pinfunction "1_1") (pintype "passive"))
      (node (ref "R_SUM0") (pin "2") (pinfunction "2_2") (pintype "passive"))
      (node (ref "R_SUM1") (pin "2") (pinfunction "2_2") (pintype "passive"))
      (node (ref "R_SUM10") (pin "2") (pinfunction "2_2") (pintype "passive"))
      (node (ref "R_SUM11") (pin "2") (pinfunction "2_2") (pintype "passive"))
      (node (ref "R_SUM12") (pin "2") (pinfunction "2_2") (pintype "passive"))
      (node (ref "R_SUM13") (pin "2") (pinfunction "2_2") (pintype "passive"))
      (node (ref "R_SUM14") (pin "2") (pinfunction "2_2") (pintype "passive"))
      (node (ref "R_SUM15") (pin "2") (pinfunction "2_2") (pintype "passive"))
      (node (ref "R_SUM2") (pin "2") (pinfunction "2_2") (pintype "passive"))
      (node (ref "R_SUM3") (pin "2") (pinfunction "2_2") (pintype "passive"))
      (node (ref "R_SUM4") (pin "2") (pinfunction "2_2") (pintype "passive"))
      (node (ref "R_SUM5") (pin "2") (pinfunction "2_2") (pintype "passive"))
      (node (ref "R_SUM6") (pin "2") (pinfunction "2_2") (pintype "passive"))
      (node (ref "R_SUM7") (pin "2") (pinfunction "2_2") (pintype "passive"))
      (node (ref "R_SUM8") (pin "2") (pinfunction "2_2") (pintype "passive"))
      (node (ref "R_SUM9") (pin "2") (pinfunction "2_2") (pintype "passive"))
      (node (ref "R_feedback") (pin "1") (pinfunction "1_1") (pintype "passive"))
      (node (ref "U0") (pin "3") (pinfunction "IN+_3") (pintype "input"))
    )
    (net (code "114") (name "VCCA") (class "Default")
      (node (ref "C_VPP") (pin "2") (pinfunction "2_2") (pintype "passive"))
      (node (ref "U0") (pin "5") (pinfunction "V+_5") (pintype "power_in"))
    )
  )
)
